# neopixel.net
KiCad netlist of a schematic drawn in EAGLE
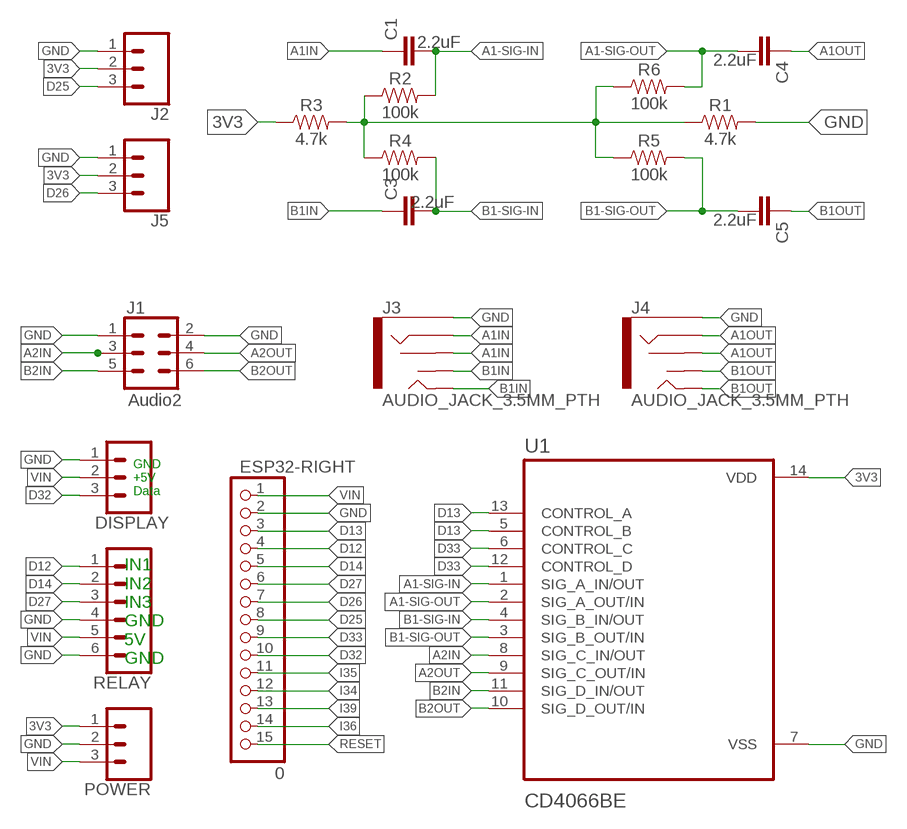
[diagram p0: schematic, sheet 1]

(export (version "E")
  (design (tool "Eeschema 10.0.6"))
  (components
    (comp (ref "C1")
      (value "2.2uF")
      (footprint "eagle-import:0805")
      (libsource (lib "eagle-import") (part "2.2UF-0805-25V-(+80/-20%)"))
    )
    (comp (ref "C3")
      (value "2.2uF")
      (footprint "eagle-import:0805")
      (libsource (lib "eagle-import") (part "2.2UF-0805-25V-(+80/-20%)"))
    )
    (comp (ref "C4")
      (value "2.2uF")
      (footprint "eagle-import:0805")
      (libsource (lib "eagle-import") (part "2.2UF-0805-25V-(+80/-20%)"))
    )
    (comp (ref "C5")
      (value "2.2uF")
      (footprint "eagle-import:0805")
      (libsource (lib "eagle-import") (part "2.2UF-0805-25V-(+80/-20%)"))
    )
    (comp (ref "DISPLAY")
      (value "CONN_03")
      (footprint "eagle-import:1X03")
      (libsource (lib "eagle-import") (part "CONN_03"))
    )
    (comp (ref "ESP32-RIGHT")
      (value "0")
      (footprint "eagle-import:1X15")
      (libsource (lib "eagle-import") (part "PINHD-1X15"))
    )
    (comp (ref "J1")
      (value "Audio2")
      (footprint "eagle-import:2X3")
      (libsource (lib "eagle-import") (part "CONN_03X2FEMALE"))
    )
    (comp (ref "J2")
      (value "CONN_03")
      (footprint "eagle-import:1X03")
      (libsource (lib "eagle-import") (part "CONN_03"))
    )
    (comp (ref "J3")
      (value "AUDIO_JACK_3.5MM_PTH")
      (footprint "eagle-import:AUDIO-JACK")
      (libsource (lib "eagle-import") (part "AUDIO_JACK_3.5MM_PTH"))
    )
    (comp (ref "J4")
      (value "AUDIO_JACK_3.5MM_PTH")
      (footprint "eagle-import:AUDIO-JACK")
      (libsource (lib "eagle-import") (part "AUDIO_JACK_3.5MM_PTH"))
    )
    (comp (ref "J5")
      (value "CONN_03")
      (footprint "eagle-import:1X03")
      (libsource (lib "eagle-import") (part "CONN_03"))
    )
    (comp (ref "POWER")
      (value "CONN_03")
      (footprint "eagle-import:1X03")
      (libsource (lib "eagle-import") (part "CONN_03"))
    )
    (comp (ref "R1")
      (value "4.7k")
      (footprint "eagle-import:0805")
      (libsource (lib "eagle-import") (part "0.3OHM-0805-1/8W-1%"))
    )
    (comp (ref "R2")
      (value "100k")
      (footprint "eagle-import:0805")
      (libsource (lib "eagle-import") (part "0.3OHM-0805-1/8W-1%"))
    )
    (comp (ref "R3")
      (value "4.7k")
      (footprint "eagle-import:0805")
      (libsource (lib "eagle-import") (part "0.3OHM-0805-1/8W-1%"))
    )
    (comp (ref "R4")
      (value "100k")
      (footprint "eagle-import:0805")
      (libsource (lib "eagle-import") (part "0.3OHM-0805-1/8W-1%"))
    )
    (comp (ref "R5")
      (value "100k")
      (footprint "eagle-import:0805")
      (libsource (lib "eagle-import") (part "0.3OHM-0805-1/8W-1%"))
    )
    (comp (ref "R6")
      (value "100k")
      (footprint "eagle-import:0805")
      (libsource (lib "eagle-import") (part "0.3OHM-0805-1/8W-1%"))
    )
    (comp (ref "RELAY")
      (value "CONN_06NO_SILK_FEMALE_PTH")
      (footprint "eagle-import:1X06_NO_SILK")
      (libsource (lib "eagle-import") (part "CONN_06NO_SILK_FEMALE_PTH"))
    )
    (comp (ref "U1")
      (value "CD4066BE")
      (footprint "eagle-import:DIP794W45P254L1969H508Q14")
      (fields (field (name "MF") "Texas Instruments"))
      (libsource (lib "eagle-import") (part "CD4066BE"))
    )
  )
  (nets
    (net (code "1") (name "3V3") (class "Default")
      (node (ref "J2") (pin "2") (pinfunction "2_2") (pintype "passive"))
      (node (ref "J5") (pin "2") (pinfunction "2_2") (pintype "passive"))
      (node (ref "POWER") (pin "1") (pinfunction "1_1") (pintype "passive"))
      (node (ref "R3") (pin "1") (pinfunction "1_1") (pintype "passive"))
      (node (ref "U1") (pin "14") (pinfunction "VDD_14") (pintype "power_in"))
    )
    (net (code "2") (name "A1-SIG-IN") (class "Default")
      (node (ref "C1") (pin "2") (pinfunction "2_2") (pintype "passive"))
      (node (ref "R2") (pin "2") (pinfunction "2_2") (pintype "passive"))
      (node (ref "U1") (pin "1") (pinfunction "SIG_A_IN/OUT_1") (pintype "input"))
    )
    (net (code "3") (name "A1-SIG-OUT") (class "Default")
      (node (ref "C4") (pin "2") (pinfunction "2_2") (pintype "passive"))
      (node (ref "R6") (pin "2") (pinfunction "2_2") (pintype "passive"))
      (node (ref "U1") (pin "2") (pinfunction "SIG_A_OUT/IN_2") (pintype "input"))
    )
    (net (code "4") (name "A1IN") (class "Default")
      (node (ref "C1") (pin "1") (pinfunction "1_1") (pintype "passive"))
      (node (ref "J3") (pin "RING") (pinfunction "RING_RING") (pintype "bidirectional"))
      (node (ref "J3") (pin "RSH") (pinfunction "RSH_RSH") (pintype "bidirectional"))
    )
    (net (code "5") (name "A1OUT") (class "Default")
      (node (ref "C4") (pin "1") (pinfunction "1_1") (pintype "passive"))
      (node (ref "J4") (pin "RING") (pinfunction "RING_RING") (pintype "bidirectional"))
      (node (ref "J4") (pin "RSH") (pinfunction "RSH_RSH") (pintype "bidirectional"))
    )
    (net (code "6") (name "A2IN") (class "Default")
      (node (ref "J1") (pin "3") (pinfunction "3_3") (pintype "bidirectional"))
      (node (ref "U1") (pin "8") (pinfunction "SIG_C_IN/OUT_8") (pintype "input"))
    )
    (net (code "7") (name "A2OUT") (class "Default")
      (node (ref "J1") (pin "4") (pinfunction "4_4") (pintype "bidirectional"))
      (node (ref "U1") (pin "9") (pinfunction "SIG_C_OUT/IN_9") (pintype "input"))
    )
    (net (code "8") (name "B1-SIG-IN") (class "Default")
      (node (ref "C3") (pin "2") (pinfunction "2_2") (pintype "passive"))
      (node (ref "R4") (pin "2") (pinfunction "2_2") (pintype "passive"))
      (node (ref "U1") (pin "4") (pinfunction "SIG_B_IN/OUT_4") (pintype "input"))
    )
    (net (code "9") (name "B1-SIG-OUT") (class "Default")
      (node (ref "C5") (pin "2") (pinfunction "2_2") (pintype "passive"))
      (node (ref "R5") (pin "2") (pinfunction "2_2") (pintype "passive"))
      (node (ref "U1") (pin "3") (pinfunction "SIG_B_OUT/IN_3") (pintype "input"))
    )
    (net (code "10") (name "B1IN") (class "Default")
      (node (ref "C3") (pin "1") (pinfunction "1_1") (pintype "passive"))
      (node (ref "J3") (pin "TIP") (pinfunction "TIP_TIP") (pintype "bidirectional"))
      (node (ref "J3") (pin "TSH") (pinfunction "TSH_TSH") (pintype "bidirectional"))
    )
    (net (code "11") (name "B1OUT") (class "Default")
      (node (ref "C5") (pin "1") (pinfunction "1_1") (pintype "passive"))
      (node (ref "J4") (pin "TIP") (pinfunction "TIP_TIP") (pintype "bidirectional"))
      (node (ref "J4") (pin "TSH") (pinfunction "TSH_TSH") (pintype "bidirectional"))
    )
    (net (code "12") (name "B2IN") (class "Default")
      (node (ref "J1") (pin "5") (pinfunction "5_5") (pintype "bidirectional"))
      (node (ref "U1") (pin "11") (pinfunction "SIG_D_IN/OUT_11") (pintype "input"))
    )
    (net (code "13") (name "B2OUT") (class "Default")
      (node (ref "J1") (pin "6") (pinfunction "6_6") (pintype "bidirectional"))
      (node (ref "U1") (pin "10") (pinfunction "SIG_D_OUT/IN_10") (pintype "input"))
    )
    (net (code "14") (name "D12") (class "Default")
      (node (ref "ESP32-RIGHT") (pin "4") (pinfunction "4_4") (pintype "passive"))
      (node (ref "RELAY") (pin "1") (pinfunction "1_1") (pintype "passive"))
    )
    (net (code "15") (name "D13") (class "Default")
      (node (ref "ESP32-RIGHT") (pin "3") (pinfunction "3_3") (pintype "passive"))
      (node (ref "U1") (pin "13") (pinfunction "CONTROL_A_13") (pintype "input"))
      (node (ref "U1") (pin "5") (pinfunction "CONTROL_B_5") (pintype "input"))
    )
    (net (code "16") (name "D14") (class "Default")
      (node (ref "ESP32-RIGHT") (pin "5") (pinfunction "5_5") (pintype "passive"))
      (node (ref "RELAY") (pin "2") (pinfunction "2_2") (pintype "passive"))
    )
    (net (code "17") (name "D25") (class "Default")
      (node (ref "ESP32-RIGHT") (pin "8") (pinfunction "8_8") (pintype "passive"))
      (node (ref "J2") (pin "3") (pinfunction "3_3") (pintype "passive"))
    )
    (net (code "18") (name "D26") (class "Default")
      (node (ref "ESP32-RIGHT") (pin "7") (pinfunction "7_7") (pintype "passive"))
      (node (ref "J5") (pin "3") (pinfunction "3_3") (pintype "passive"))
    )
    (net (code "19") (name "D27") (class "Default")
      (node (ref "ESP32-RIGHT") (pin "6") (pinfunction "6_6") (pintype "passive"))
      (node (ref "RELAY") (pin "3") (pinfunction "3_3") (pintype "passive"))
    )
    (net (code "20") (name "D32") (class "Default")
      (node (ref "DISPLAY") (pin "3") (pinfunction "3_3") (pintype "passive"))
      (node (ref "ESP32-RIGHT") (pin "10") (pinfunction "10_10") (pintype "passive"))
    )
    (net (code "21") (name "D33") (class "Default")
      (node (ref "ESP32-RIGHT") (pin "9") (pinfunction "9_9") (pintype "passive"))
      (node (ref "U1") (pin "12") (pinfunction "CONTROL_D_12") (pintype "input"))
      (node (ref "U1") (pin "6") (pinfunction "CONTROL_C_6") (pintype "input"))
    )
    (net (code "22") (name "GND") (class "Default")
      (node (ref "DISPLAY") (pin "1") (pinfunction "1_1") (pintype "passive"))
      (node (ref "ESP32-RIGHT") (pin "2") (pinfunction "2_2") (pintype "passive"))
      (node (ref "J1") (pin "1") (pinfunction "1_1") (pintype "bidirectional"))
      (node (ref "J1") (pin "2") (pinfunction "2_2") (pintype "bidirectional"))
      (node (ref "J2") (pin "1") (pinfunction "1_1") (pintype "passive"))
      (node (ref "J3") (pin "SLEEVE") (pinfunction "SLEEVE_SLEEVE") (pintype "bidirectional"))
      (node (ref "J4") (pin "SLEEVE") (pinfunction "SLEEVE_SLEEVE") (pintype "bidirectional"))
      (node (ref "J5") (pin "1") (pinfunction "1_1") (pintype "passive"))
      (node (ref "POWER") (pin "2") (pinfunction "2_2") (pintype "passive"))
      (node (ref "R1") (pin "2") (pinfunction "2_2") (pintype "passive"))
      (node (ref "RELAY") (pin "4") (pinfunction "4_4") (pintype "passive"))
      (node (ref "RELAY") (pin "6") (pinfunction "6_6") (pintype "passive"))
      (node (ref "U1") (pin "7") (pinfunction "VSS_7") (pintype "power_in"))
    )
    (net (code "23") (name "I34") (class "Default")
      (node (ref "ESP32-RIGHT") (pin "12") (pinfunction "12_12") (pintype "passive"))
    )
    (net (code "24") (name "I35") (class "Default")
      (node (ref "ESP32-RIGHT") (pin "11") (pinfunction "11_11") (pintype "passive"))
    )
    (net (code "25") (name "I36") (class "Default")
      (node (ref "ESP32-RIGHT") (pin "14") (pinfunction "14_14") (pintype "passive"))
    )
    (net (code "26") (name "I39") (class "Default")
      (node (ref "ESP32-RIGHT") (pin "13") (pinfunction "13_13") (pintype "passive"))
    )
    (net (code "27") (name "Net-(R1-Pad1)") (class "Default")
      (node (ref "R1") (pin "1") (pinfunction "1_1") (pintype "passive"))
      (node (ref "R2") (pin "1") (pinfunction "1_1") (pintype "passive"))
      (node (ref "R3") (pin "2") (pinfunction "2_2") (pintype "passive"))
      (node (ref "R4") (pin "1") (pinfunction "1_1") (pintype "passive"))
      (node (ref "R5") (pin "1") (pinfunction "1_1") (pintype "passive"))
      (node (ref "R6") (pin "1") (pinfunction "1_1") (pintype "passive"))
    )
    (net (code "28") (name "RESET") (class "Default")
      (node (ref "ESP32-RIGHT") (pin "15") (pinfunction "15_15") (pintype "passive"))
    )
    (net (code "29") (name "VIN") (class "Default")
      (node (ref "DISPLAY") (pin "2") (pinfunction "2_2") (pintype "passive"))
      (node (ref "ESP32-RIGHT") (pin "1") (pinfunction "1_1") (pintype "passive"))
      (node (ref "POWER") (pin "3") (pinfunction "3_3") (pintype "passive"))
      (node (ref "RELAY") (pin "5") (pinfunction "5_5") (pintype "passive"))
    )
  )
)
